# Control_Board_add.net
KiCad netlist of a schematic drawn in Altium Designer
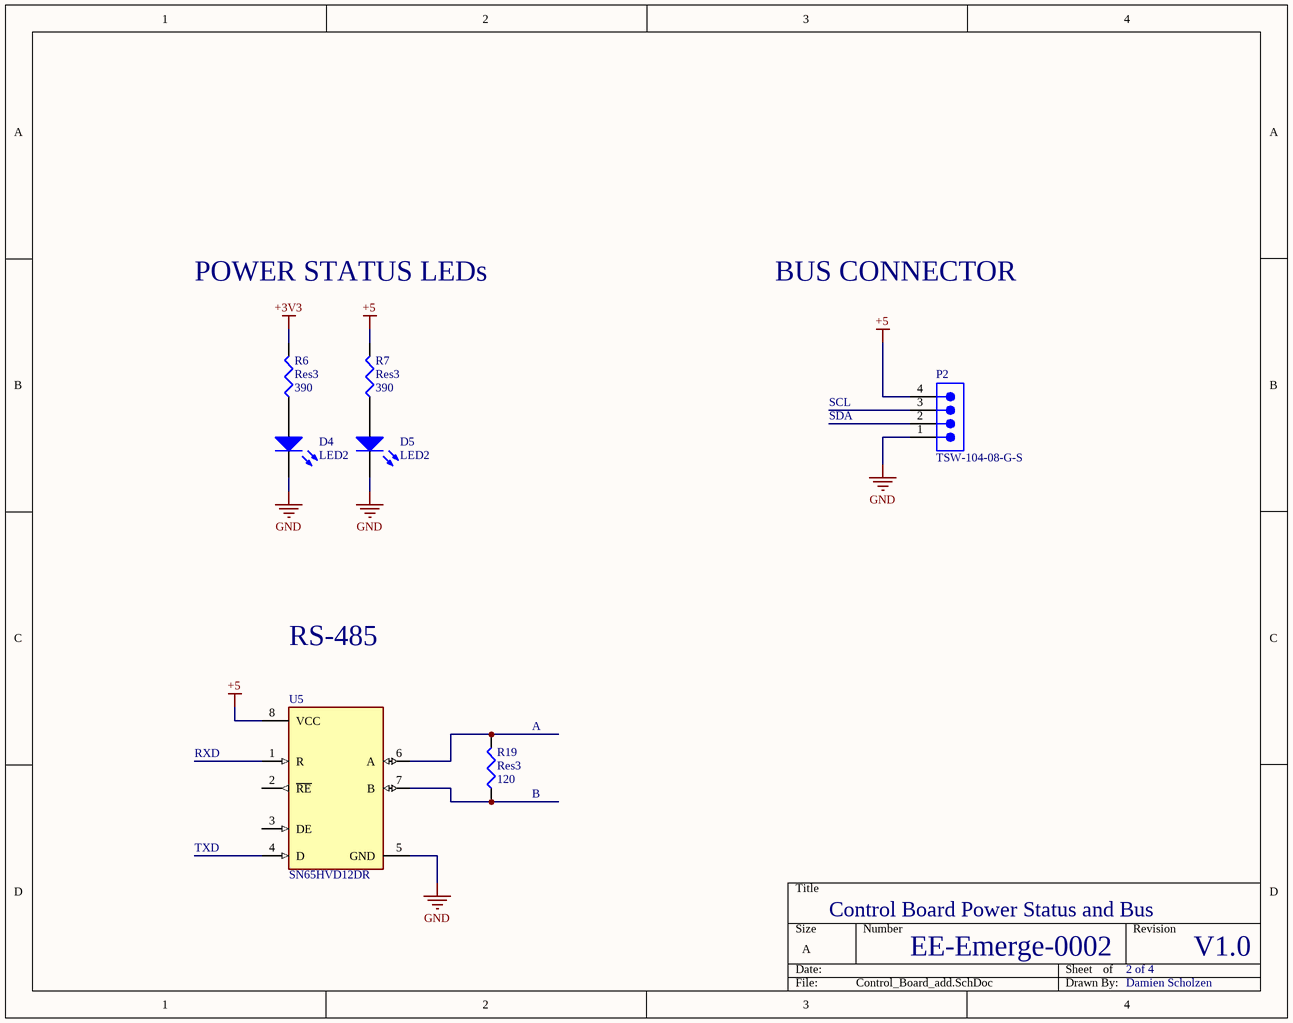
[diagram p0: Control_Board_add.SchDoc]

(export (version "E")
  (design (tool "Eeschema 10.0.6"))
  (components
    (comp (ref "D4")
      (value "LED2")
      (footprint "3.2X1.6X1.1")
      (description "Typical RED, GREEN, YELLOW, AMBER GaAs LED")
      (fields (field (name "PUBLISHER") "Altium Limited"))
      (libsource (lib "EE_Emerge_SkillsProject (1)") (part "LED2"))
    )
    (comp (ref "D5")
      (value "LED2")
      (footprint "3.2X1.6X1.1")
      (description "Typical RED, GREEN, YELLOW, AMBER GaAs LED")
      (fields (field (name "PUBLISHER") "Altium Limited"))
      (libsource (lib "EE_Emerge_SkillsProject (1)") (part "LED2"))
    )
    (comp (ref "P2")
      (value "TSW-104-08-G-S")
      (footprint "SMTC-TSW-104-08-X-S")
      (description "0.025\" SQ Post Header, Through-hole, Vertical, -55 to 125 degC, 2.54 mm Pitch, 4-Pin, Male, RoHS")
      (fields (field (name "MANUFACTURER") "Samtec"))
      (libsource (lib "Altium Content Vault") (part "SMTC-TSW-104-08-X-S"))
    )
    (comp (ref "R6")
      (value "Res3")
      (footprint "6-0805_N")
      (description "Resistor")
      (fields (field (name "ALTIUM_VALUE") "390") (field (name "PUBLISHER") "Altium Limited"))
      (libsource (lib "EE_Emerge_SkillsProject (1)") (part "Res3_4"))
    )
    (comp (ref "R7")
      (value "Res3")
      (footprint "6-0805_N")
      (description "Resistor")
      (fields (field (name "ALTIUM_VALUE") "390") (field (name "PUBLISHER") "Altium Limited"))
      (libsource (lib "EE_Emerge_SkillsProject (1)") (part "Res3_4"))
    )
    (comp (ref "R19")
      (value "Res3")
      (footprint "6-0805_N")
      (description "Resistor")
      (fields (field (name "ALTIUM_VALUE") "120") (field (name "PUBLISHER") "Altium Limited"))
      (libsource (lib "EE_Emerge_SkillsProject (1)") (part "Res3_4"))
    )
    (comp (ref "U5")
      (value "SN65HVD12DR")
      (footprint "FP-D0008A-MFG")
      (description "Single Transmitter/Receiver RS-485 8-Pin SOIC T/R")
      (fields (field (name "OCTOPART") "https://octopart.com/sn65hvd12dr-texas+instruments-713591"))
      (libsource (lib "Altium Content Vault") (part "9b5e85850bc5e2b73de6fccf45375aa"))
    )
  )
  (nets
    (net (code "1") (name "+3V3") (class "Default")
      (node (ref "R6") (pin "2") (pinfunction "2_2") (pintype "passive"))
    )
    (net (code "2") (name "+5") (class "Default")
      (node (ref "P2") (pin "4") (pinfunction "4_4") (pintype "passive"))
      (node (ref "R7") (pin "2") (pinfunction "2_2") (pintype "passive"))
      (node (ref "U5") (pin "8") (pinfunction "VCC_8") (pintype "power_in"))
    )
    (net (code "3") (name "GND") (class "Default")
      (node (ref "D4") (pin "2") (pinfunction "K_2") (pintype "passive"))
      (node (ref "D5") (pin "2") (pinfunction "K_2") (pintype "passive"))
      (node (ref "P2") (pin "1") (pinfunction "1_1") (pintype "passive"))
      (node (ref "U5") (pin "5") (pinfunction "GND_5") (pintype "power_in"))
    )
    (net (code "4") (name "Net-(D4-A)") (class "Default")
      (node (ref "D4") (pin "1") (pinfunction "A_1") (pintype "passive"))
      (node (ref "R6") (pin "1") (pinfunction "1_1") (pintype "passive"))
    )
    (net (code "5") (name "Net-(D5-A)") (class "Default")
      (node (ref "D5") (pin "1") (pinfunction "A_1") (pintype "passive"))
      (node (ref "R7") (pin "1") (pinfunction "1_1") (pintype "passive"))
    )
    (net (code "6") (name "Net-(U5-A)") (class "Default")
      (node (ref "R19") (pin "2") (pinfunction "2_2") (pintype "passive"))
      (node (ref "U5") (pin "6") (pinfunction "A_6") (pintype "bidirectional"))
    )
    (net (code "7") (name "Net-(U5-B)") (class "Default")
      (node (ref "R19") (pin "1") (pinfunction "1_1") (pintype "passive"))
      (node (ref "U5") (pin "7") (pinfunction "B_7") (pintype "bidirectional"))
    )
    (net (code "8") (name "unconnected-(P2-Pad2)") (class "Default")
      (node (ref "P2") (pin "2") (pinfunction "2_2") (pintype "passive"))
    )
    (net (code "9") (name "unconnected-(P2-Pad3)") (class "Default")
      (node (ref "P2") (pin "3") (pinfunction "3_3") (pintype "passive"))
    )
    (net (code "10") (name "unconnected-(U5-D-Pad4)") (class "Default")
      (node (ref "U5") (pin "4") (pinfunction "D_4") (pintype "input"))
    )
    (net (code "11") (name "unconnected-(U5-DE-Pad3)") (class "Default")
      (node (ref "U5") (pin "3") (pinfunction "DE_3") (pintype "input"))
    )
    (net (code "12") (name "unconnected-(U5-R-Pad1)") (class "Default")
      (node (ref "U5") (pin "1") (pinfunction "R_1") (pintype "input"))
    )
    (net (code "13") (name "unconnected-(U5-~{RE}-Pad2)") (class "Default")
      (node (ref "U5") (pin "2") (pinfunction "~{RE}_2") (pintype "output"))
    )
  )
)
